# Qwiic_Power_Switch.net
KiCad netlist of a schematic drawn in EAGLE
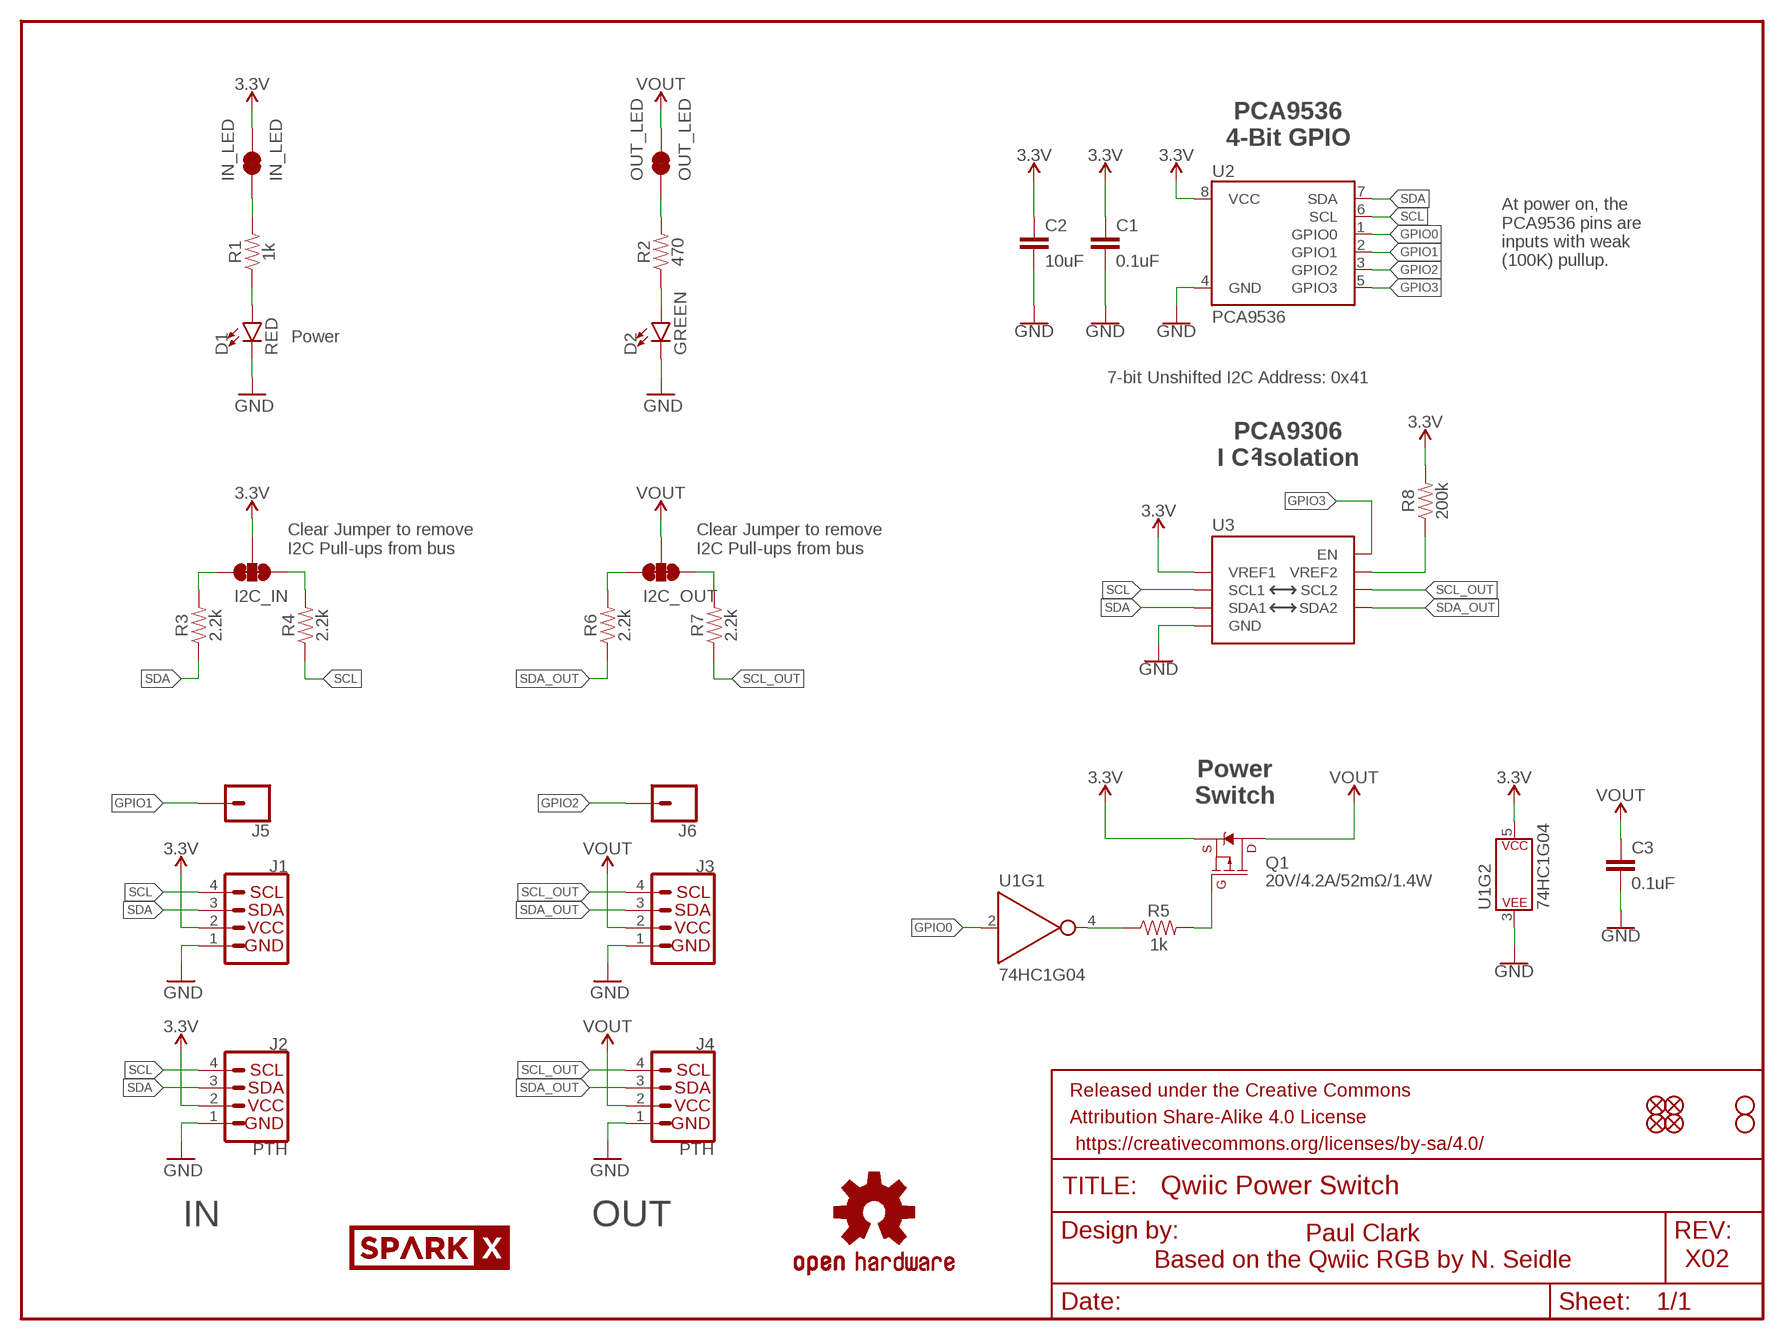
[diagram p0: schematic, sheet 1]

(export (version "E")
  (design (tool "Eeschema 10.0.6"))
  (components
    (comp (ref "C1")
      (value "0.1uF")
      (footprint "eagle-import:0603")
      (libsource (lib "eagle-import") (part "0.1UF-0603-25V-(+80/-20%)"))
    )
    (comp (ref "C2")
      (value "10uF")
      (footprint "eagle-import:0603")
      (libsource (lib "eagle-import") (part "10UF-0603-6.3V-20%"))
    )
    (comp (ref "C3")
      (value "0.1uF")
      (footprint "eagle-import:0603")
      (libsource (lib "eagle-import") (part "0.1UF-0603-25V-(+80/-20%)"))
    )
    (comp (ref "D1")
      (value "RED")
      (footprint "eagle-import:LED-0603")
      (libsource (lib "eagle-import") (part "LED-RED0603"))
    )
    (comp (ref "D2")
      (value "GREEN")
      (footprint "eagle-import:LED-0603")
      (libsource (lib "eagle-import") (part "LED-GREEN0603"))
    )
    (comp (ref "FRAME1")
      (value "FRAME-LETTER")
      (footprint "eagle-import:CREATIVE_COMMONS")
      (libsource (lib "eagle-import") (part "FRAME-LETTER"))
    )
    (comp (ref "I2C_IN")
      (value "JUMPER-SMT_3_2-NC_TRACE_SILK")
      (footprint "eagle-import:SMT-JUMPER_3_2-NC_TRACE_SILK")
      (libsource (lib "eagle-import") (part "JUMPER-SMT_3_2-NC_TRACE_SILK"))
    )
    (comp (ref "I2C_OUT")
      (value "JUMPER-SMT_3_2-NC_TRACE_SILK")
      (footprint "eagle-import:SMT-JUMPER_3_2-NC_TRACE_SILK")
      (libsource (lib "eagle-import") (part "JUMPER-SMT_3_2-NC_TRACE_SILK"))
    )
    (comp (ref "IN_LED")
      (value "IN_LED")
      (footprint "eagle-import:SMT-JUMPER_2_NC_TRACE_SILK")
      (libsource (lib "eagle-import") (part "JUMPER-SMT_2_NC_TRACE_SILK"))
    )
    (comp (ref "J1")
      (value "Qwiic Right Angle")
      (footprint "eagle-import:JST04_1MM_RA")
      (libsource (lib "eagle-import") (part "I2C_STANDARDQWIIC"))
    )
    (comp (ref "J2")
      (value "PTH")
      (footprint "eagle-import:1X04_NO_SILK")
      (libsource (lib "eagle-import") (part "I2C_STANDARD_NO_SILK"))
    )
    (comp (ref "J3")
      (value "Qwiic Right Angle")
      (footprint "eagle-import:JST04_1MM_RA")
      (libsource (lib "eagle-import") (part "I2C_STANDARDQWIIC"))
    )
    (comp (ref "J4")
      (value "PTH")
      (footprint "eagle-import:1X04_NO_SILK")
      (libsource (lib "eagle-import") (part "I2C_STANDARD_NO_SILK"))
    )
    (comp (ref "J5")
      (value "CONN_01PTH_NO_SILK_YES_STOP")
      (footprint "eagle-import:1X01_NO_SILK")
      (libsource (lib "eagle-import") (part "CONN_01PTH_NO_SILK_YES_STOP"))
    )
    (comp (ref "J6")
      (value "CONN_01PTH_NO_SILK_YES_STOP")
      (footprint "eagle-import:1X01_NO_SILK")
      (libsource (lib "eagle-import") (part "CONN_01PTH_NO_SILK_YES_STOP"))
    )
    (comp (ref "JP1")
      (value "FIDUCIAL1X2")
      (footprint "eagle-import:FIDUCIAL-1X2")
      (libsource (lib "eagle-import") (part "FIDUCIAL1X2"))
    )
    (comp (ref "JP2")
      (value "FIDUCIAL1X2")
      (footprint "eagle-import:FIDUCIAL-1X2")
      (libsource (lib "eagle-import") (part "FIDUCIAL1X2"))
    )
    (comp (ref "JP3")
      (value "STAND-OFF")
      (footprint "eagle-import:STAND-OFF")
      (libsource (lib "eagle-import") (part "STAND-OFF"))
    )
    (comp (ref "JP4")
      (value "STAND-OFF")
      (footprint "eagle-import:STAND-OFF")
      (libsource (lib "eagle-import") (part "STAND-OFF"))
    )
    (comp (ref "JP5")
      (value "FIDUCIAL1X2")
      (footprint "eagle-import:FIDUCIAL-1X2")
      (libsource (lib "eagle-import") (part "FIDUCIAL1X2"))
    )
    (comp (ref "JP6")
      (value "FIDUCIAL1X2")
      (footprint "eagle-import:FIDUCIAL-1X2")
      (libsource (lib "eagle-import") (part "FIDUCIAL1X2"))
    )
    (comp (ref "LOGO1")
      (value "OSHW-LOGOMINI")
      (footprint "eagle-import:OSHW-LOGO-MINI")
      (libsource (lib "eagle-import") (part "OSHW-LOGOMINI"))
    )
    (comp (ref "OUT_LED")
      (value "OUT_LED")
      (footprint "eagle-import:SMT-JUMPER_2_NC_TRACE_SILK")
      (libsource (lib "eagle-import") (part "JUMPER-SMT_2_NC_TRACE_SILK"))
    )
    (comp (ref "Q1")
      (value "20V/4.2A/52mΩ/1.4W")
      (footprint "eagle-import:SOT23-3")
      (libsource (lib "eagle-import") (part "MOSFET_PCH-DMG2305UX-7"))
    )
    (comp (ref "R1")
      (value "1k")
      (footprint "eagle-import:0603")
      (libsource (lib "eagle-import") (part "1KOHM-0603-1/10W-1%"))
    )
    (comp (ref "R2")
      (value "470")
      (footprint "eagle-import:0603")
      (libsource (lib "eagle-import") (part "470OHM-0603-1/10W-1%"))
    )
    (comp (ref "R3")
      (value "2.2k")
      (footprint "eagle-import:0603")
      (libsource (lib "eagle-import") (part "2.2KOHM-0603-1/10W-1%"))
    )
    (comp (ref "R4")
      (value "2.2k")
      (footprint "eagle-import:0603")
      (libsource (lib "eagle-import") (part "2.2KOHM-0603-1/10W-1%"))
    )
    (comp (ref "R5")
      (value "1k")
      (footprint "eagle-import:0603")
      (libsource (lib "eagle-import") (part "1KOHM-0603-1/10W-1%"))
    )
    (comp (ref "R6")
      (value "2.2k")
      (footprint "eagle-import:0603")
      (libsource (lib "eagle-import") (part "2.2KOHM-0603-1/10W-1%"))
    )
    (comp (ref "R7")
      (value "2.2k")
      (footprint "eagle-import:0603")
      (libsource (lib "eagle-import") (part "2.2KOHM-0603-1/10W-1%"))
    )
    (comp (ref "R8")
      (value "200k")
      (footprint "eagle-import:0603")
      (libsource (lib "eagle-import") (part "200KOHM-0603-1/10W-1%"))
    )
    (comp (ref "U$2")
      (value "SPARKX-LOGO4")
      (footprint "eagle-import:SPARKX-MEDIUM")
      (libsource (lib "eagle-import") (part "SPARKX-LOGO4"))
    )
    (comp (ref "U1")
      (value "74HC1G04")
      (footprint "eagle-import:SOT353")
      (libsource (lib "eagle-import") (part "741G04HC"))
    )
    (comp (ref "U2")
      (value "PCA9536")
      (footprint "eagle-import:MSOP8")
      (libsource (lib "eagle-import") (part "PCA9536"))
    )
    (comp (ref "U3")
      (value "PCA9306VSSOP_8PIN")
      (footprint "eagle-import:VSSOP_8PIN")
      (libsource (lib "eagle-import") (part "PCA9306VSSOP_8PIN"))
    )
  )
  (nets
    (net (code "1") (name "3.3V") (class "Default")
      (node (ref "C1") (pin "1") (pinfunction "1_1") (pintype "passive"))
      (node (ref "C2") (pin "1") (pinfunction "1_1") (pintype "passive"))
      (node (ref "I2C_IN") (pin "2") (pinfunction "2_2") (pintype "passive"))
      (node (ref "IN_LED") (pin "2") (pinfunction "2_2") (pintype "passive"))
      (node (ref "J1") (pin "2") (pinfunction "2_2") (pintype "power_in"))
      (node (ref "J2") (pin "2") (pinfunction "2_2") (pintype "power_in"))
      (node (ref "Q1") (pin "2") (pinfunction "S_2") (pintype "bidirectional"))
      (node (ref "R8") (pin "2") (pinfunction "2_2") (pintype "passive"))
      (node (ref "U1") (pin "5") (pinfunction "P$V+_5") (pintype "bidirectional"))
      (node (ref "U2") (pin "8") (pinfunction "VCC_8") (pintype "bidirectional"))
      (node (ref "U3") (pin "P2") (pinfunction "VREF1_P2") (pintype "power_in"))
    )
    (net (code "2") (name "GND") (class "Default")
      (node (ref "C1") (pin "2") (pinfunction "2_2") (pintype "passive"))
      (node (ref "C2") (pin "2") (pinfunction "2_2") (pintype "passive"))
      (node (ref "C3") (pin "2") (pinfunction "2_2") (pintype "passive"))
      (node (ref "D1") (pin "C") (pinfunction "C_C") (pintype "passive"))
      (node (ref "D2") (pin "C") (pinfunction "C_C") (pintype "passive"))
      (node (ref "J1") (pin "1") (pinfunction "1_1") (pintype "power_in"))
      (node (ref "J2") (pin "1") (pinfunction "1_1") (pintype "power_in"))
      (node (ref "J3") (pin "1") (pinfunction "1_1") (pintype "power_in"))
      (node (ref "J4") (pin "1") (pinfunction "1_1") (pintype "power_in"))
      (node (ref "U1") (pin "3") (pinfunction "P$V-_3") (pintype "bidirectional"))
      (node (ref "U2") (pin "4") (pinfunction "GND_4") (pintype "bidirectional"))
      (node (ref "U3") (pin "P1") (pinfunction "GND_P1") (pintype "power_in"))
    )
    (net (code "3") (name "GPIO0") (class "Default")
      (node (ref "U1") (pin "2") (pinfunction "A_2") (pintype "bidirectional"))
      (node (ref "U2") (pin "1") (pinfunction "GPIO0_1") (pintype "bidirectional"))
    )
    (net (code "4") (name "GPIO1") (class "Default")
      (node (ref "J5") (pin "1") (pinfunction "1_1") (pintype "passive"))
      (node (ref "U2") (pin "2") (pinfunction "GPIO1_2") (pintype "bidirectional"))
    )
    (net (code "5") (name "GPIO2") (class "Default")
      (node (ref "J6") (pin "1") (pinfunction "1_1") (pintype "passive"))
      (node (ref "U2") (pin "3") (pinfunction "GPIO2_3") (pintype "bidirectional"))
    )
    (net (code "6") (name "GPIO3") (class "Default")
      (node (ref "U2") (pin "5") (pinfunction "GPIO3_5") (pintype "bidirectional"))
      (node (ref "U3") (pin "P8") (pinfunction "EN_P8") (pintype "input"))
    )
    (net (code "7") (name "Net-(D1-PadA)") (class "Default")
      (node (ref "D1") (pin "A") (pinfunction "A_A") (pintype "passive"))
      (node (ref "R1") (pin "1") (pinfunction "1_1") (pintype "passive"))
    )
    (net (code "8") (name "Net-(D2-PadA)") (class "Default")
      (node (ref "D2") (pin "A") (pinfunction "A_A") (pintype "passive"))
      (node (ref "R2") (pin "1") (pinfunction "1_1") (pintype "passive"))
    )
    (net (code "9") (name "Net-(I2C_IN-Pad1)") (class "Default")
      (node (ref "I2C_IN") (pin "1") (pinfunction "1_1") (pintype "passive"))
      (node (ref "R4") (pin "2") (pinfunction "2_2") (pintype "passive"))
    )
    (net (code "10") (name "Net-(I2C_IN-Pad3)") (class "Default")
      (node (ref "I2C_IN") (pin "3") (pinfunction "3_3") (pintype "passive"))
      (node (ref "R3") (pin "2") (pinfunction "2_2") (pintype "passive"))
    )
    (net (code "11") (name "Net-(I2C_OUT-Pad1)") (class "Default")
      (node (ref "I2C_OUT") (pin "1") (pinfunction "1_1") (pintype "passive"))
      (node (ref "R7") (pin "2") (pinfunction "2_2") (pintype "passive"))
    )
    (net (code "12") (name "Net-(I2C_OUT-Pad3)") (class "Default")
      (node (ref "I2C_OUT") (pin "3") (pinfunction "3_3") (pintype "passive"))
      (node (ref "R6") (pin "2") (pinfunction "2_2") (pintype "passive"))
    )
    (net (code "13") (name "Net-(IN_LED-Pad1)") (class "Default")
      (node (ref "IN_LED") (pin "1") (pinfunction "1_1") (pintype "passive"))
      (node (ref "R1") (pin "2") (pinfunction "2_2") (pintype "passive"))
    )
    (net (code "14") (name "Net-(OUT_LED-Pad1)") (class "Default")
      (node (ref "OUT_LED") (pin "1") (pinfunction "1_1") (pintype "passive"))
      (node (ref "R2") (pin "2") (pinfunction "2_2") (pintype "passive"))
    )
    (net (code "15") (name "Net-(Q1-G)") (class "Default")
      (node (ref "Q1") (pin "1") (pinfunction "G_1") (pintype "bidirectional"))
      (node (ref "R5") (pin "2") (pinfunction "2_2") (pintype "passive"))
    )
    (net (code "16") (name "Net-(U1A-Y)") (class "Default")
      (node (ref "R5") (pin "1") (pinfunction "1_1") (pintype "passive"))
      (node (ref "U1") (pin "4") (pinfunction "Y_4") (pintype "bidirectional"))
    )
    (net (code "17") (name "Net-(U3-VREF2)") (class "Default")
      (node (ref "R8") (pin "1") (pinfunction "1_1") (pintype "passive"))
      (node (ref "U3") (pin "P7") (pinfunction "VREF2_P7") (pintype "power_in"))
    )
    (net (code "18") (name "SCL") (class "Default")
      (node (ref "J1") (pin "4") (pinfunction "4_4") (pintype "passive"))
      (node (ref "J2") (pin "4") (pinfunction "4_4") (pintype "passive"))
      (node (ref "R4") (pin "1") (pinfunction "1_1") (pintype "passive"))
      (node (ref "U2") (pin "6") (pinfunction "SCL_6") (pintype "bidirectional"))
      (node (ref "U3") (pin "P3") (pinfunction "SCL1_P3") (pintype "bidirectional"))
    )
    (net (code "19") (name "SCL_OUT") (class "Default")
      (node (ref "J3") (pin "4") (pinfunction "4_4") (pintype "passive"))
      (node (ref "J4") (pin "4") (pinfunction "4_4") (pintype "passive"))
      (node (ref "R7") (pin "1") (pinfunction "1_1") (pintype "passive"))
      (node (ref "U3") (pin "P6") (pinfunction "SCL2_P6") (pintype "bidirectional"))
    )
    (net (code "20") (name "SDA") (class "Default")
      (node (ref "J1") (pin "3") (pinfunction "3_3") (pintype "passive"))
      (node (ref "J2") (pin "3") (pinfunction "3_3") (pintype "passive"))
      (node (ref "R3") (pin "1") (pinfunction "1_1") (pintype "passive"))
      (node (ref "U2") (pin "7") (pinfunction "SDA_7") (pintype "bidirectional"))
      (node (ref "U3") (pin "P4") (pinfunction "SDA1_P4") (pintype "bidirectional"))
    )
    (net (code "21") (name "SDA_OUT") (class "Default")
      (node (ref "J3") (pin "3") (pinfunction "3_3") (pintype "passive"))
      (node (ref "J4") (pin "3") (pinfunction "3_3") (pintype "passive"))
      (node (ref "R6") (pin "1") (pinfunction "1_1") (pintype "passive"))
      (node (ref "U3") (pin "P5") (pinfunction "SDA2_P5") (pintype "bidirectional"))
    )
    (net (code "22") (name "VOUT") (class "Default")
      (node (ref "C3") (pin "1") (pinfunction "1_1") (pintype "passive"))
      (node (ref "I2C_OUT") (pin "2") (pinfunction "2_2") (pintype "passive"))
      (node (ref "J3") (pin "2") (pinfunction "2_2") (pintype "power_in"))
      (node (ref "J4") (pin "2") (pinfunction "2_2") (pintype "power_in"))
      (node (ref "OUT_LED") (pin "2") (pinfunction "2_2") (pintype "passive"))
      (node (ref "Q1") (pin "3") (pinfunction "D_3") (pintype "bidirectional"))
    )
  )
)
